# LIC_rack_backplane_Con-00.net
KiCad netlist of a schematic drawn in EAGLE
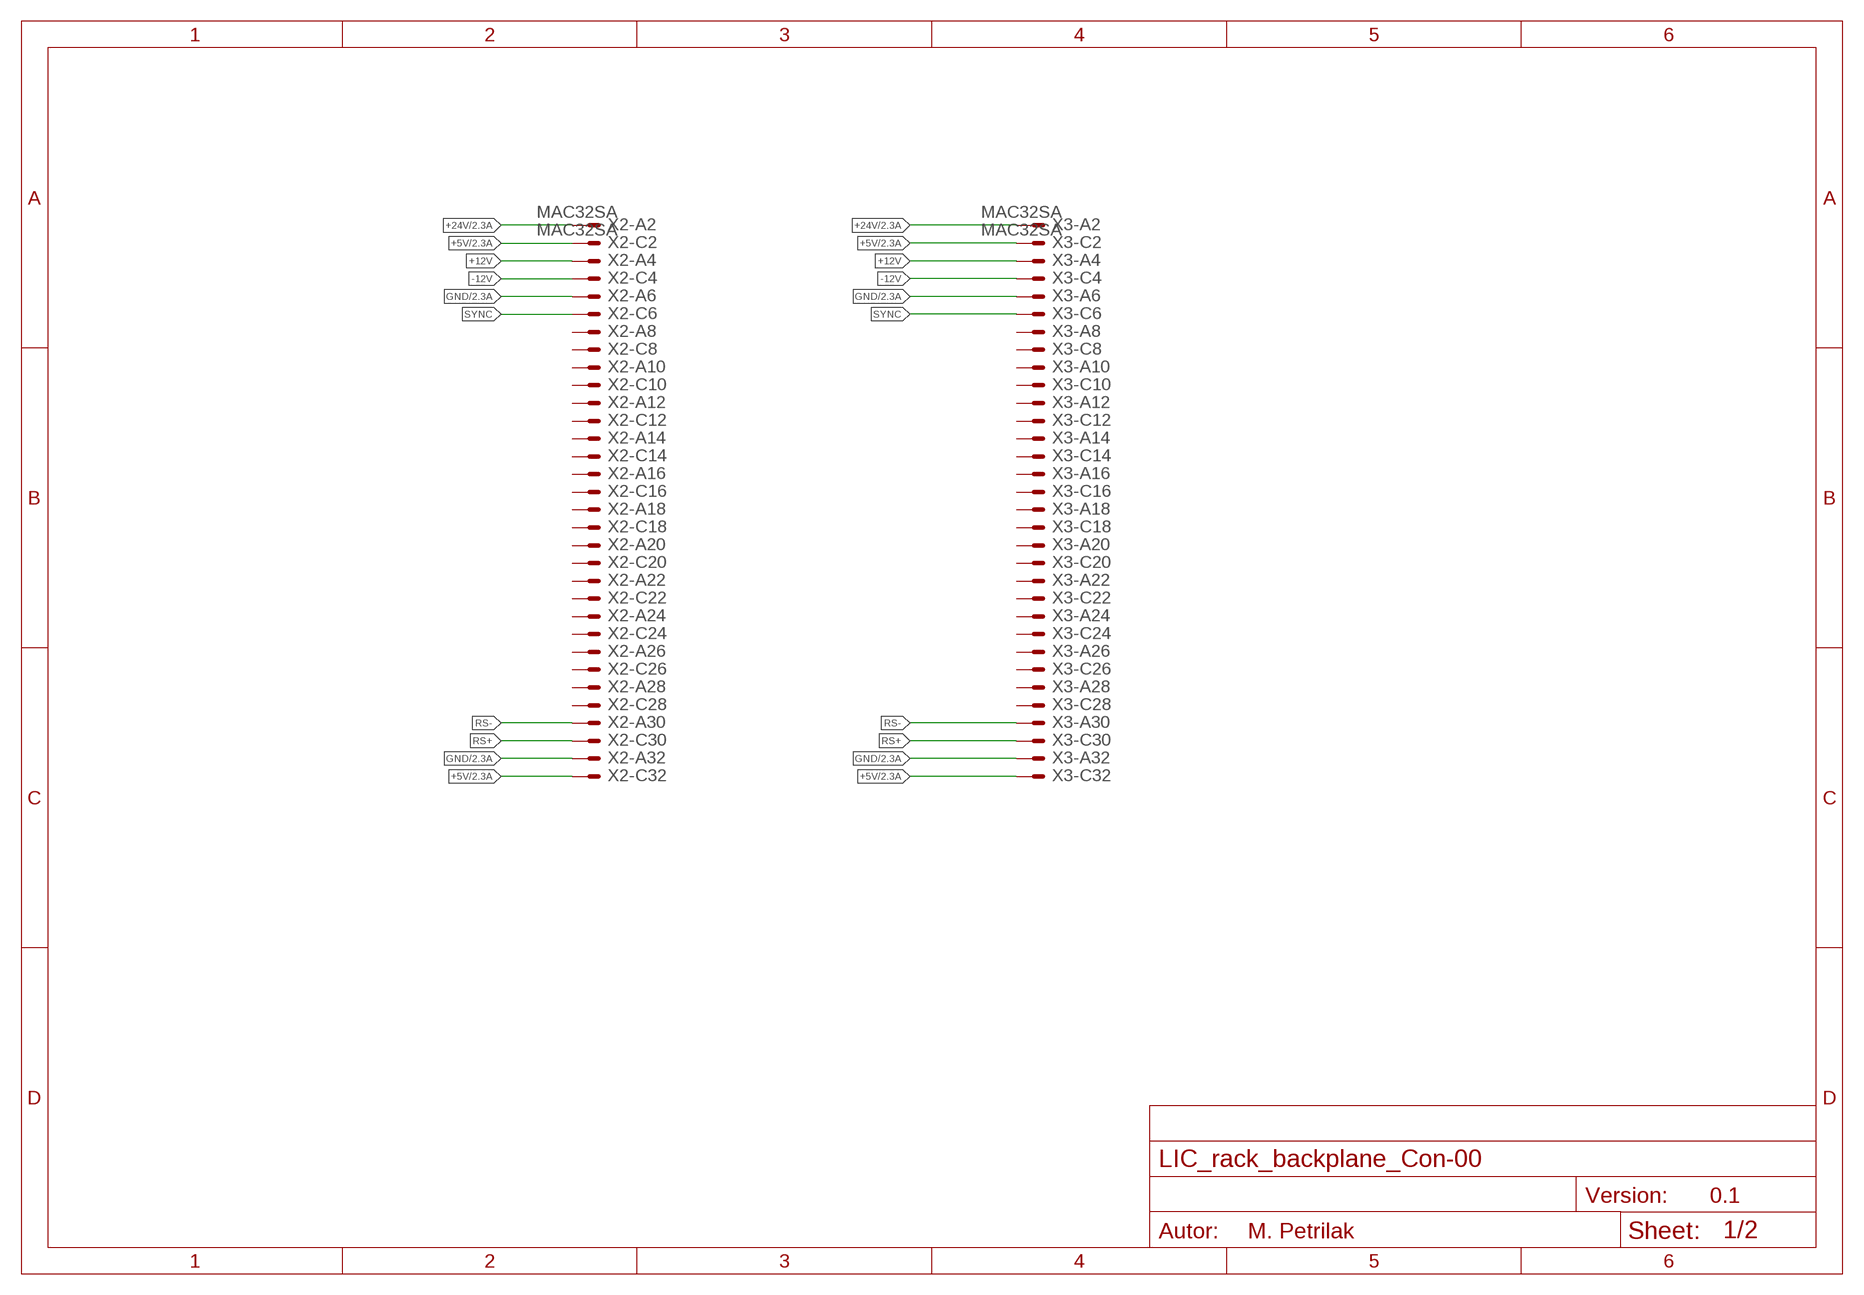
[diagram p0: schematic, sheet 1]
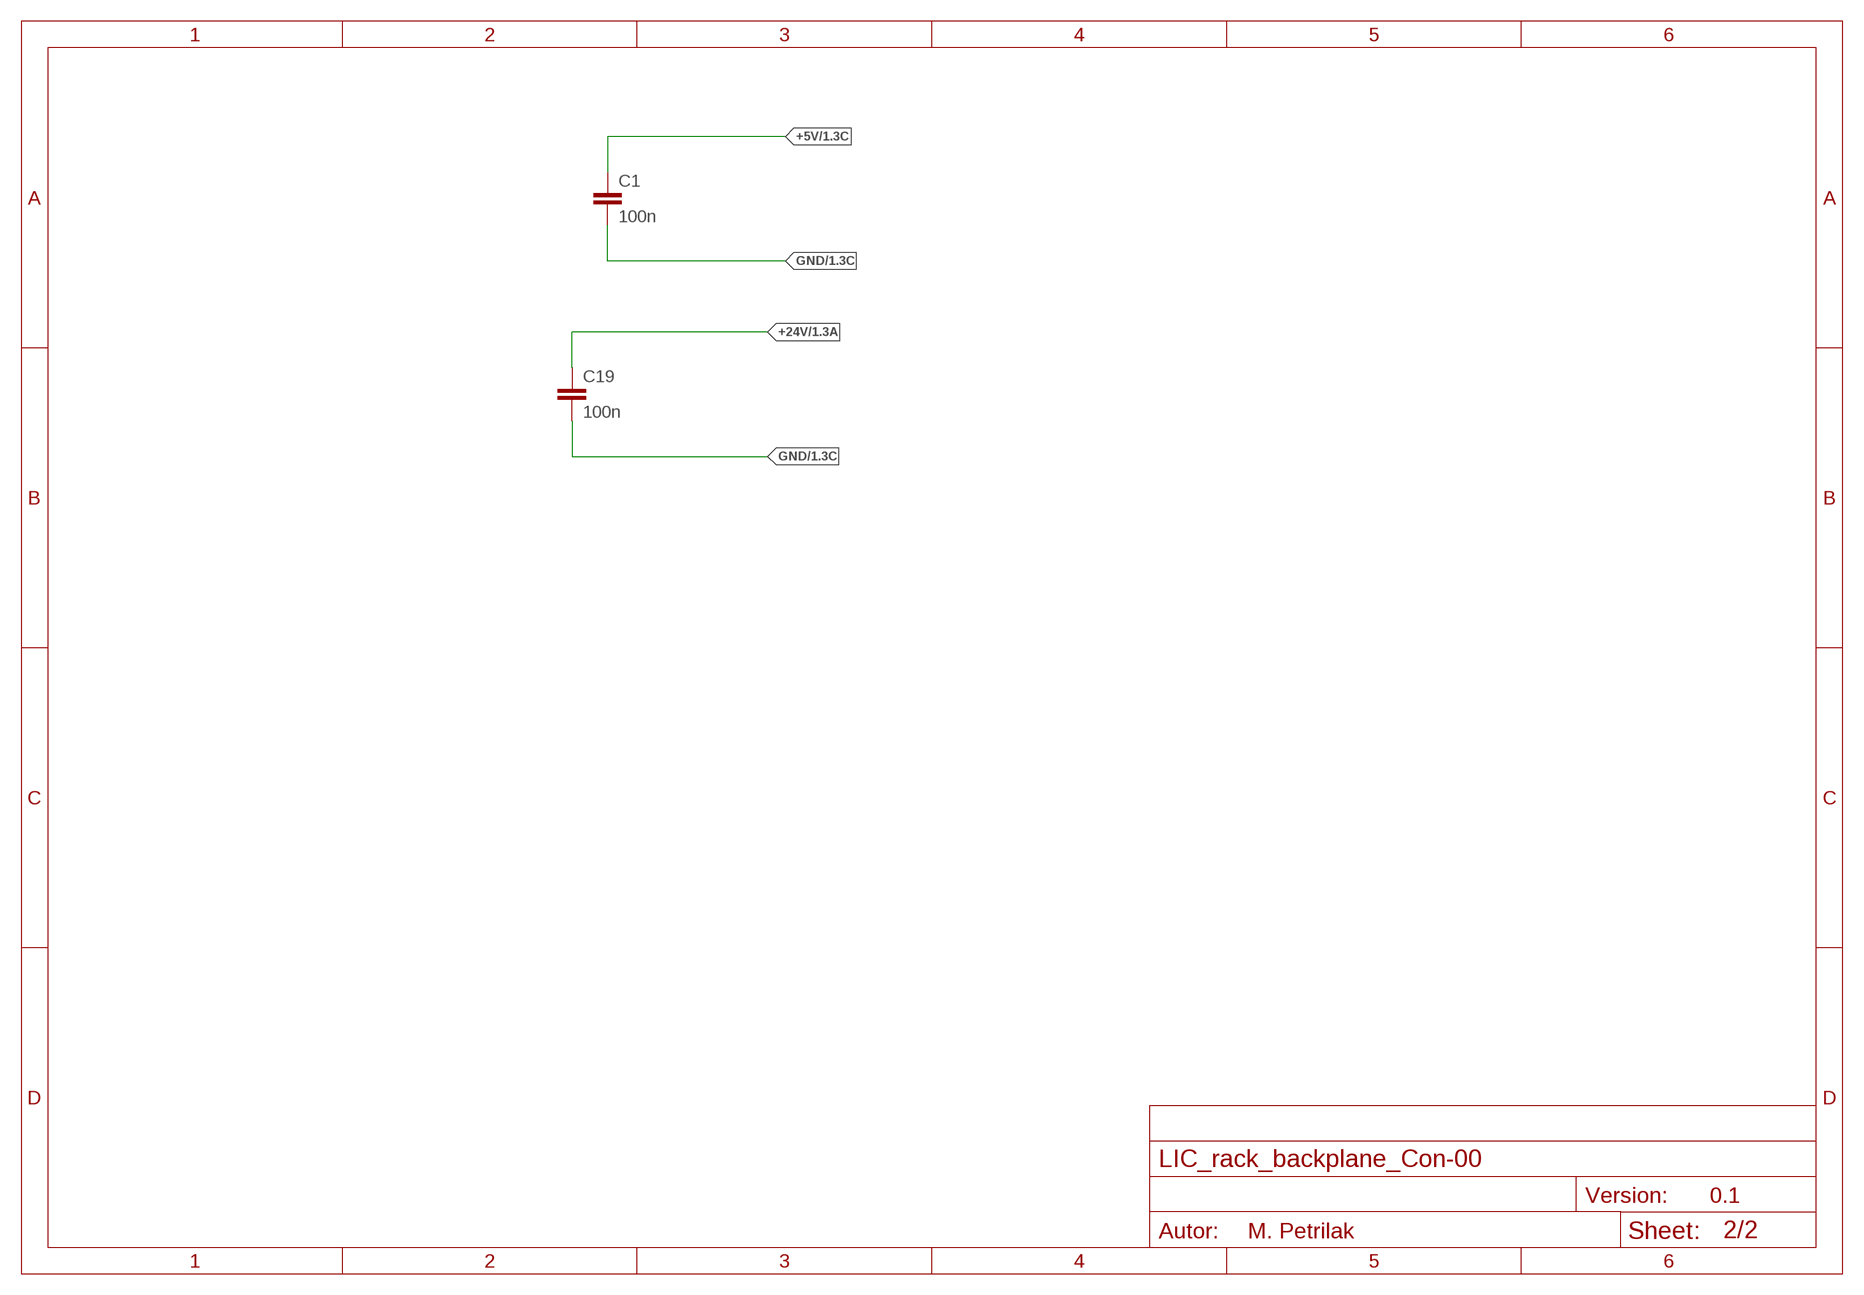
[diagram p1: schematic, sheet 2]

(export (version "E")
  (design (tool "Eeschema 10.0.6"))
  (components
    (comp (ref "C1")
      (value "100n")
      (footprint "eagle-import:C1206")
      (libsource (lib "eagle-import") (part "C-EUC1206"))
    )
    (comp (ref "C19")
      (value "100n")
      (footprint "eagle-import:C1206")
      (libsource (lib "eagle-import") (part "C-EUC1206"))
    )
    (comp (ref "X2")
      (value "MAC32SA")
      (footprint "eagle-import:MAC32SA")
      (libsource (lib "eagle-import") (part "MAC32SA"))
    )
    (comp (ref "X3")
      (value "MAC32SA")
      (footprint "eagle-import:MAC32SA")
      (libsource (lib "eagle-import") (part "MAC32SA"))
    )
  )
  (nets
    (net (code "1") (name "+5V") (class "Default")
      (node (ref "C1") (pin "1") (pinfunction "1_1") (pintype "passive"))
      (node (ref "X2") (pin "C2") (pinfunction "S_C2") (pintype "passive"))
      (node (ref "X2") (pin "C32") (pinfunction "S_C32") (pintype "passive"))
      (node (ref "X3") (pin "C2") (pinfunction "S_C2") (pintype "passive"))
      (node (ref "X3") (pin "C32") (pinfunction "S_C32") (pintype "passive"))
    )
    (net (code "2") (name "+12V") (class "Default")
      (node (ref "X2") (pin "A4") (pinfunction "S_A4") (pintype "passive"))
      (node (ref "X3") (pin "A4") (pinfunction "S_A4") (pintype "passive"))
    )
    (net (code "3") (name "+24V") (class "Default")
      (node (ref "C19") (pin "1") (pinfunction "1_1") (pintype "passive"))
      (node (ref "X2") (pin "A2") (pinfunction "S_A2") (pintype "passive"))
      (node (ref "X3") (pin "A2") (pinfunction "S_A2") (pintype "passive"))
    )
    (net (code "4") (name "-12V") (class "Default")
      (node (ref "X2") (pin "C4") (pinfunction "S_C4") (pintype "passive"))
      (node (ref "X3") (pin "C4") (pinfunction "S_C4") (pintype "passive"))
    )
    (net (code "5") (name "GND") (class "Default")
      (node (ref "C1") (pin "2") (pinfunction "2_2") (pintype "passive"))
      (node (ref "C19") (pin "2") (pinfunction "2_2") (pintype "passive"))
      (node (ref "X2") (pin "A32") (pinfunction "S_A32") (pintype "passive"))
      (node (ref "X2") (pin "A6") (pinfunction "S_A6") (pintype "passive"))
      (node (ref "X3") (pin "A32") (pinfunction "S_A32") (pintype "passive"))
      (node (ref "X3") (pin "A6") (pinfunction "S_A6") (pintype "passive"))
    )
    (net (code "6") (name "RS+") (class "Default")
      (node (ref "X2") (pin "C30") (pinfunction "S_C30") (pintype "passive"))
      (node (ref "X3") (pin "C30") (pinfunction "S_C30") (pintype "passive"))
    )
    (net (code "7") (name "RS-") (class "Default")
      (node (ref "X2") (pin "A30") (pinfunction "S_A30") (pintype "passive"))
      (node (ref "X3") (pin "A30") (pinfunction "S_A30") (pintype "passive"))
    )
    (net (code "8") (name "SYNC") (class "Default")
      (node (ref "X2") (pin "C6") (pinfunction "S_C6") (pintype "passive"))
      (node (ref "X3") (pin "C6") (pinfunction "S_C6") (pintype "passive"))
    )
    (net (code "9") (name "unconnected-(X2A-S-PadA10)") (class "Default")
      (node (ref "X2") (pin "A10") (pinfunction "S_A10") (pintype "passive"))
    )
    (net (code "10") (name "unconnected-(X2AA-S-PadC28)") (class "Default")
      (node (ref "X2") (pin "C28") (pinfunction "S_C28") (pintype "passive"))
    )
    (net (code "11") (name "unconnected-(X2AF-S-PadC8)") (class "Default")
      (node (ref "X2") (pin "C8") (pinfunction "S_C8") (pintype "passive"))
    )
    (net (code "12") (name "unconnected-(X2B-S-PadA12)") (class "Default")
      (node (ref "X2") (pin "A12") (pinfunction "S_A12") (pintype "passive"))
    )
    (net (code "13") (name "unconnected-(X2C-S-PadA14)") (class "Default")
      (node (ref "X2") (pin "A14") (pinfunction "S_A14") (pintype "passive"))
    )
    (net (code "14") (name "unconnected-(X2D-S-PadA16)") (class "Default")
      (node (ref "X2") (pin "A16") (pinfunction "S_A16") (pintype "passive"))
    )
    (net (code "15") (name "unconnected-(X2E-S-PadA18)") (class "Default")
      (node (ref "X2") (pin "A18") (pinfunction "S_A18") (pintype "passive"))
    )
    (net (code "16") (name "unconnected-(X2G-S-PadA20)") (class "Default")
      (node (ref "X2") (pin "A20") (pinfunction "S_A20") (pintype "passive"))
    )
    (net (code "17") (name "unconnected-(X2H-S-PadA22)") (class "Default")
      (node (ref "X2") (pin "A22") (pinfunction "S_A22") (pintype "passive"))
    )
    (net (code "18") (name "unconnected-(X2I-S-PadA24)") (class "Default")
      (node (ref "X2") (pin "A24") (pinfunction "S_A24") (pintype "passive"))
    )
    (net (code "19") (name "unconnected-(X2J-S-PadA26)") (class "Default")
      (node (ref "X2") (pin "A26") (pinfunction "S_A26") (pintype "passive"))
    )
    (net (code "20") (name "unconnected-(X2K-S-PadA28)") (class "Default")
      (node (ref "X2") (pin "A28") (pinfunction "S_A28") (pintype "passive"))
    )
    (net (code "21") (name "unconnected-(X2P-S-PadA8)") (class "Default")
      (node (ref "X2") (pin "A8") (pinfunction "S_A8") (pintype "passive"))
    )
    (net (code "22") (name "unconnected-(X2Q-S-PadC10)") (class "Default")
      (node (ref "X2") (pin "C10") (pinfunction "S_C10") (pintype "passive"))
    )
    (net (code "23") (name "unconnected-(X2R-S-PadC12)") (class "Default")
      (node (ref "X2") (pin "C12") (pinfunction "S_C12") (pintype "passive"))
    )
    (net (code "24") (name "unconnected-(X2S-S-PadC14)") (class "Default")
      (node (ref "X2") (pin "C14") (pinfunction "S_C14") (pintype "passive"))
    )
    (net (code "25") (name "unconnected-(X2T-S-PadC16)") (class "Default")
      (node (ref "X2") (pin "C16") (pinfunction "S_C16") (pintype "passive"))
    )
    (net (code "26") (name "unconnected-(X2U-S-PadC18)") (class "Default")
      (node (ref "X2") (pin "C18") (pinfunction "S_C18") (pintype "passive"))
    )
    (net (code "27") (name "unconnected-(X2W-S-PadC20)") (class "Default")
      (node (ref "X2") (pin "C20") (pinfunction "S_C20") (pintype "passive"))
    )
    (net (code "28") (name "unconnected-(X2X-S-PadC22)") (class "Default")
      (node (ref "X2") (pin "C22") (pinfunction "S_C22") (pintype "passive"))
    )
    (net (code "29") (name "unconnected-(X2Y-S-PadC24)") (class "Default")
      (node (ref "X2") (pin "C24") (pinfunction "S_C24") (pintype "passive"))
    )
    (net (code "30") (name "unconnected-(X2Z-S-PadC26)") (class "Default")
      (node (ref "X2") (pin "C26") (pinfunction "S_C26") (pintype "passive"))
    )
    (net (code "31") (name "unconnected-(X3A-S-PadA10)") (class "Default")
      (node (ref "X3") (pin "A10") (pinfunction "S_A10") (pintype "passive"))
    )
    (net (code "32") (name "unconnected-(X3AA-S-PadC28)") (class "Default")
      (node (ref "X3") (pin "C28") (pinfunction "S_C28") (pintype "passive"))
    )
    (net (code "33") (name "unconnected-(X3AF-S-PadC8)") (class "Default")
      (node (ref "X3") (pin "C8") (pinfunction "S_C8") (pintype "passive"))
    )
    (net (code "34") (name "unconnected-(X3B-S-PadA12)") (class "Default")
      (node (ref "X3") (pin "A12") (pinfunction "S_A12") (pintype "passive"))
    )
    (net (code "35") (name "unconnected-(X3C-S-PadA14)") (class "Default")
      (node (ref "X3") (pin "A14") (pinfunction "S_A14") (pintype "passive"))
    )
    (net (code "36") (name "unconnected-(X3D-S-PadA16)") (class "Default")
      (node (ref "X3") (pin "A16") (pinfunction "S_A16") (pintype "passive"))
    )
    (net (code "37") (name "unconnected-(X3E-S-PadA18)") (class "Default")
      (node (ref "X3") (pin "A18") (pinfunction "S_A18") (pintype "passive"))
    )
    (net (code "38") (name "unconnected-(X3G-S-PadA20)") (class "Default")
      (node (ref "X3") (pin "A20") (pinfunction "S_A20") (pintype "passive"))
    )
    (net (code "39") (name "unconnected-(X3H-S-PadA22)") (class "Default")
      (node (ref "X3") (pin "A22") (pinfunction "S_A22") (pintype "passive"))
    )
    (net (code "40") (name "unconnected-(X3I-S-PadA24)") (class "Default")
      (node (ref "X3") (pin "A24") (pinfunction "S_A24") (pintype "passive"))
    )
    (net (code "41") (name "unconnected-(X3J-S-PadA26)") (class "Default")
      (node (ref "X3") (pin "A26") (pinfunction "S_A26") (pintype "passive"))
    )
    (net (code "42") (name "unconnected-(X3K-S-PadA28)") (class "Default")
      (node (ref "X3") (pin "A28") (pinfunction "S_A28") (pintype "passive"))
    )
    (net (code "43") (name "unconnected-(X3P-S-PadA8)") (class "Default")
      (node (ref "X3") (pin "A8") (pinfunction "S_A8") (pintype "passive"))
    )
    (net (code "44") (name "unconnected-(X3Q-S-PadC10)") (class "Default")
      (node (ref "X3") (pin "C10") (pinfunction "S_C10") (pintype "passive"))
    )
    (net (code "45") (name "unconnected-(X3R-S-PadC12)") (class "Default")
      (node (ref "X3") (pin "C12") (pinfunction "S_C12") (pintype "passive"))
    )
    (net (code "46") (name "unconnected-(X3S-S-PadC14)") (class "Default")
      (node (ref "X3") (pin "C14") (pinfunction "S_C14") (pintype "passive"))
    )
    (net (code "47") (name "unconnected-(X3T-S-PadC16)") (class "Default")
      (node (ref "X3") (pin "C16") (pinfunction "S_C16") (pintype "passive"))
    )
    (net (code "48") (name "unconnected-(X3U-S-PadC18)") (class "Default")
      (node (ref "X3") (pin "C18") (pinfunction "S_C18") (pintype "passive"))
    )
    (net (code "49") (name "unconnected-(X3W-S-PadC20)") (class "Default")
      (node (ref "X3") (pin "C20") (pinfunction "S_C20") (pintype "passive"))
    )
    (net (code "50") (name "unconnected-(X3X-S-PadC22)") (class "Default")
      (node (ref "X3") (pin "C22") (pinfunction "S_C22") (pintype "passive"))
    )
    (net (code "51") (name "unconnected-(X3Y-S-PadC24)") (class "Default")
      (node (ref "X3") (pin "C24") (pinfunction "S_C24") (pintype "passive"))
    )
    (net (code "52") (name "unconnected-(X3Z-S-PadC26)") (class "Default")
      (node (ref "X3") (pin "C26") (pinfunction "S_C26") (pintype "passive"))
    )
  )
)
